# SCH_Aman-PCB-Project_2025-10-18.net
KiCad netlist of a schematic drawn in EasyEDA
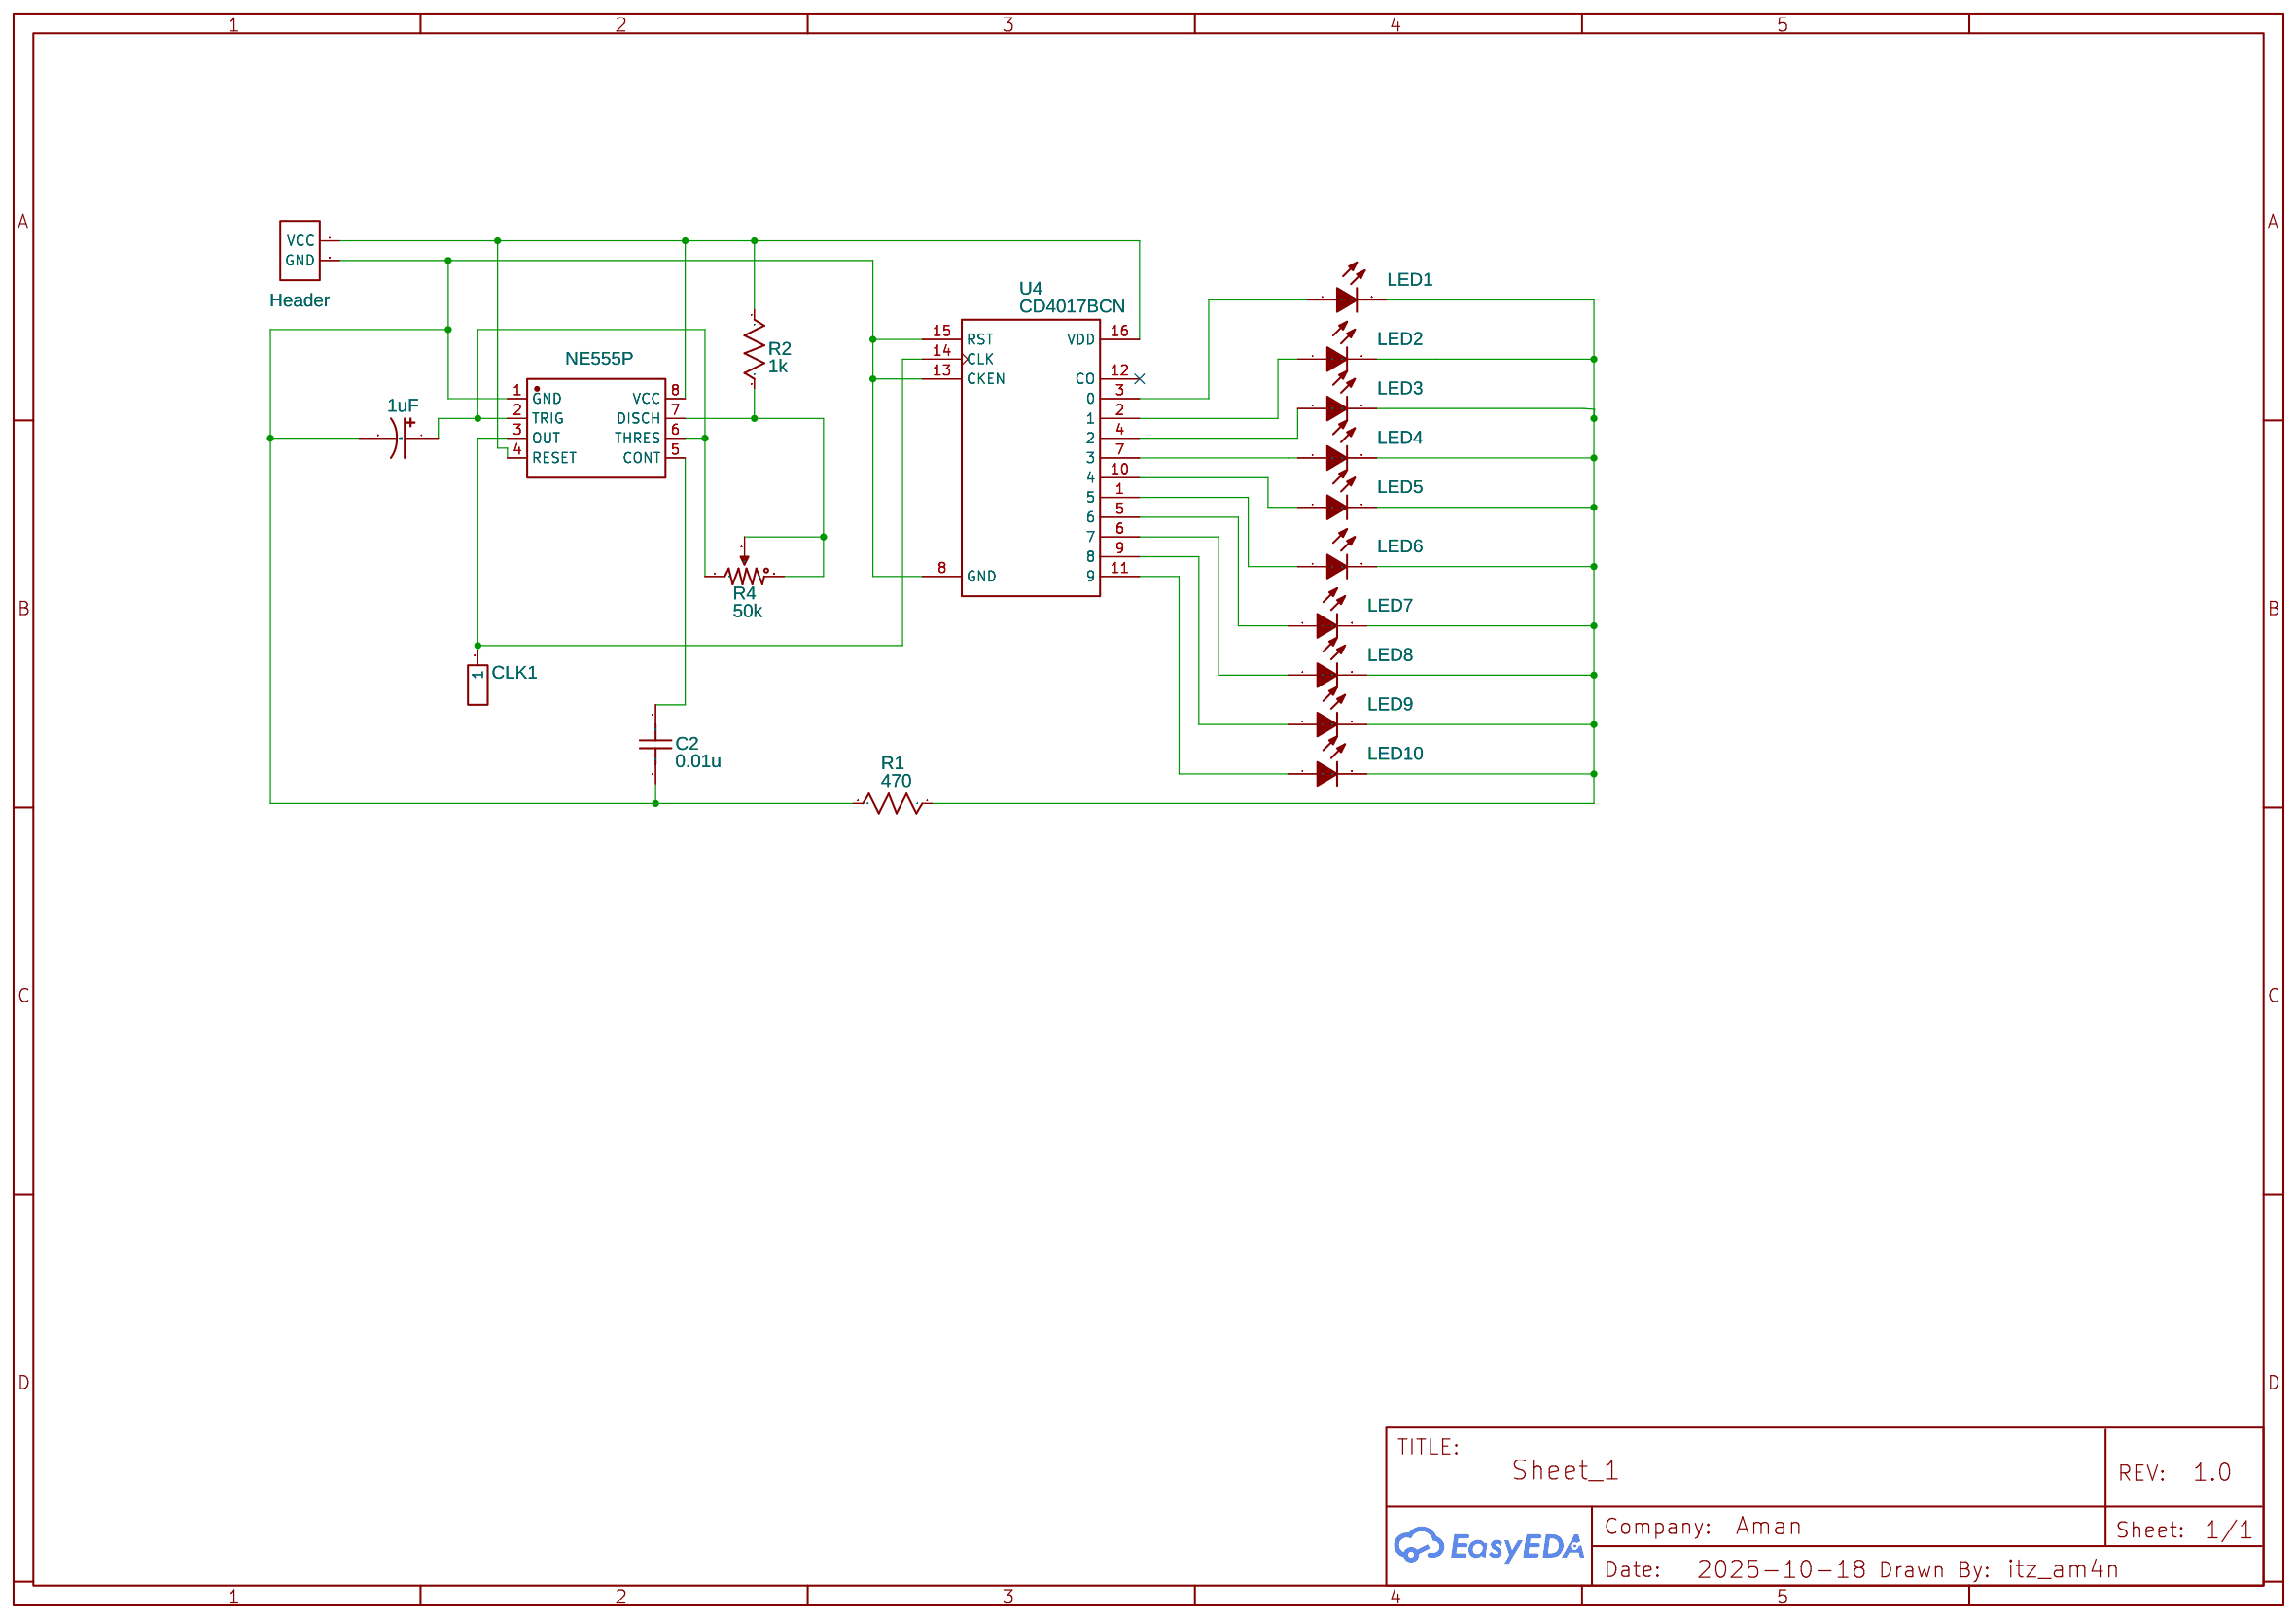
[diagram p0: schematic sheet]

(export (version "E")
  (design (tool "Eeschema 10.0.6"))
  (components
    (comp (ref "C1")
      (value "1uF")
      (fields (field (name "Manufacturer Part") "UVZ1H010MDD") (field (name "Manufacturer") "Nichicon(尼吉康)"))
      (libsource (lib "") (part "UVZ1H010MDD"))
    )
    (comp (ref "C2") (value "0.01u") (libsource (lib "") (part "C_0603_US")))
    (comp (ref "CLK1")
      (value "C81276")
      (fields
        (field (name "Manufacturer Part") "2.54-1*1P针")
        (field (name "Manufacturer") "BOOMELE(Boom Precision Elec)")
      )
      (libsource (lib "") (part "Header-Male-2.54_1x1"))
    )
    (comp (ref "H1") (value "Header") (libsource (lib "") (part "HEADER-FEMALE-2.54_1X2")))
    (comp (ref "LED1") (value "LED_5MM") (libsource (lib "") (part "LED_5MM")))
    (comp (ref "LED2") (value "LED_5MM") (libsource (lib "") (part "LED_5MM")))
    (comp (ref "LED3") (value "LED_5MM") (libsource (lib "") (part "LED_5MM")))
    (comp (ref "LED4") (value "LED_5MM") (libsource (lib "") (part "LED_5MM")))
    (comp (ref "LED5") (value "LED_5MM") (libsource (lib "") (part "LED_5MM")))
    (comp (ref "LED6") (value "LED_5MM") (libsource (lib "") (part "LED_5MM")))
    (comp (ref "LED7") (value "LED_5MM") (libsource (lib "") (part "LED_5MM")))
    (comp (ref "LED8") (value "LED_5MM") (libsource (lib "") (part "LED_5MM")))
    (comp (ref "LED9") (value "LED_5MM") (libsource (lib "") (part "LED_5MM")))
    (comp (ref "LED10") (value "LED_5MM") (libsource (lib "") (part "LED_5MM")))
    (comp (ref "R1")
      (value "470")
      (fields (field (name "Manufacturer Part") "?"))
      (libsource (lib "") (part "Resistor_1"))
    )
    (comp (ref "R2")
      (value "1k")
      (fields (field (name "Manufacturer Part") "?"))
      (libsource (lib "") (part "Resistor"))
    )
    (comp (ref "R4")
      (value "50k")
      (fields (field (name "Manufacturer Part") "?"))
      (libsource (lib "") (part "Potentiometer"))
    )
    (comp (ref "U2")
      (value "NE555P")
      (fields (field (name "Manufacturer") "TI(德州仪器)"))
      (libsource (lib "") (part "NE555P"))
    )
    (comp (ref "U4") (value "CD4017BCN") (libsource (lib "") (part "CD4017BCN")))
  )
  (nets
    (net (code "1") (name "Net-(H1-GND)") (class "Default")
      (node (ref "C1") (pin "2") (pinfunction "2_2") (pintype "unspecified"))
      (node (ref "C2") (pin "2") (pinfunction "2_2") (pintype "unspecified"))
      (node (ref "H1") (pin "2") (pinfunction "GND_2") (pintype "unspecified"))
      (node (ref "R1") (pin "2") (pinfunction "2_2") (pintype "unspecified"))
      (node (ref "U2") (pin "1") (pinfunction "GND_1") (pintype "unspecified"))
      (node (ref "U4") (pin "13") (pinfunction "CKEN_13") (pintype "unspecified"))
      (node (ref "U4") (pin "15") (pinfunction "RST_15") (pintype "unspecified"))
      (node (ref "U4") (pin "8") (pinfunction "GND_8") (pintype "passive"))
    )
    (net (code "2") (name "Net-(H1-VCC)") (class "Default")
      (node (ref "H1") (pin "1") (pinfunction "VCC_1") (pintype "unspecified"))
      (node (ref "R2") (pin "1") (pinfunction "1_1") (pintype "unspecified"))
      (node (ref "U2") (pin "4") (pinfunction "RESET_4") (pintype "unspecified"))
      (node (ref "U2") (pin "8") (pinfunction "VCC_8") (pintype "unspecified"))
      (node (ref "U4") (pin "16") (pinfunction "VDD_16") (pintype "passive"))
    )
    (net (code "3") (name "Net-(LED1-A)") (class "Default")
      (node (ref "LED1") (pin "1") (pinfunction "A_1") (pintype "input"))
      (node (ref "U4") (pin "3") (pinfunction "0_3") (pintype "output"))
    )
    (net (code "4") (name "Net-(LED1-K)") (class "Default")
      (node (ref "LED1") (pin "2") (pinfunction "K_2") (pintype "input"))
      (node (ref "LED10") (pin "2") (pinfunction "K_2") (pintype "input"))
      (node (ref "LED2") (pin "2") (pinfunction "K_2") (pintype "input"))
      (node (ref "LED3") (pin "2") (pinfunction "K_2") (pintype "input"))
      (node (ref "LED4") (pin "2") (pinfunction "K_2") (pintype "input"))
      (node (ref "LED5") (pin "2") (pinfunction "K_2") (pintype "input"))
      (node (ref "LED6") (pin "2") (pinfunction "K_2") (pintype "input"))
      (node (ref "LED7") (pin "2") (pinfunction "K_2") (pintype "input"))
      (node (ref "LED8") (pin "2") (pinfunction "K_2") (pintype "input"))
      (node (ref "LED9") (pin "2") (pinfunction "K_2") (pintype "input"))
      (node (ref "R1") (pin "1") (pinfunction "1_1") (pintype "unspecified"))
    )
    (net (code "5") (name "Net-(LED2-A)") (class "Default")
      (node (ref "LED2") (pin "1") (pinfunction "A_1") (pintype "input"))
      (node (ref "U4") (pin "2") (pinfunction "1_2") (pintype "output"))
    )
    (net (code "6") (name "Net-(LED3-A)") (class "Default")
      (node (ref "LED3") (pin "1") (pinfunction "A_1") (pintype "input"))
      (node (ref "U4") (pin "4") (pinfunction "2_4") (pintype "output"))
    )
    (net (code "7") (name "Net-(LED4-A)") (class "Default")
      (node (ref "LED4") (pin "1") (pinfunction "A_1") (pintype "input"))
      (node (ref "U4") (pin "7") (pinfunction "3_7") (pintype "output"))
    )
    (net (code "8") (name "Net-(LED5-A)") (class "Default")
      (node (ref "LED5") (pin "1") (pinfunction "A_1") (pintype "input"))
      (node (ref "U4") (pin "10") (pinfunction "4_10") (pintype "output"))
    )
    (net (code "9") (name "Net-(LED6-A)") (class "Default")
      (node (ref "LED6") (pin "1") (pinfunction "A_1") (pintype "input"))
      (node (ref "U4") (pin "1") (pinfunction "5_1") (pintype "output"))
    )
    (net (code "10") (name "Net-(LED7-A)") (class "Default")
      (node (ref "LED7") (pin "1") (pinfunction "A_1") (pintype "input"))
      (node (ref "U4") (pin "5") (pinfunction "6_5") (pintype "output"))
    )
    (net (code "11") (name "Net-(LED8-A)") (class "Default")
      (node (ref "LED8") (pin "1") (pinfunction "A_1") (pintype "input"))
      (node (ref "U4") (pin "6") (pinfunction "7_6") (pintype "output"))
    )
    (net (code "12") (name "Net-(LED9-A)") (class "Default")
      (node (ref "LED9") (pin "1") (pinfunction "A_1") (pintype "input"))
      (node (ref "U4") (pin "9") (pinfunction "8_9") (pintype "output"))
    )
    (net (code "13") (name "Net-(LED10-A)") (class "Default")
      (node (ref "LED10") (pin "1") (pinfunction "A_1") (pintype "input"))
      (node (ref "U4") (pin "11") (pinfunction "9_11") (pintype "output"))
    )
    (net (code "14") (name "Net-(R4-2)") (class "Default")
      (node (ref "R2") (pin "2") (pinfunction "2_2") (pintype "unspecified"))
      (node (ref "R4") (pin "2") (pinfunction "3_2") (pintype "unspecified"))
      (node (ref "R4") (pin "3") (pinfunction "2_3") (pintype "unspecified"))
      (node (ref "U2") (pin "7") (pinfunction "DISCH_7") (pintype "unspecified"))
    )
    (net (code "15") (name "Net-(U2-CONT)") (class "Default")
      (node (ref "C2") (pin "1") (pinfunction "1_1") (pintype "unspecified"))
      (node (ref "U2") (pin "5") (pinfunction "CONT_5") (pintype "unspecified"))
    )
    (net (code "16") (name "Net-(U2-OUT)") (class "Default")
      (node (ref "CLK1") (pin "1") (pinfunction "1_1") (pintype "unspecified"))
      (node (ref "U2") (pin "3") (pinfunction "OUT_3") (pintype "unspecified"))
      (node (ref "U4") (pin "14") (pinfunction "CLK_14") (pintype "unspecified"))
    )
    (net (code "17") (name "Net-(U2-THRES)") (class "Default")
      (node (ref "C1") (pin "1") (pinfunction "1_1") (pintype "unspecified"))
      (node (ref "R4") (pin "1") (pinfunction "1_1") (pintype "unspecified"))
      (node (ref "U2") (pin "2") (pinfunction "TRIG_2") (pintype "unspecified"))
      (node (ref "U2") (pin "6") (pinfunction "THRES_6") (pintype "unspecified"))
    )
    (net (code "18") (name "unconnected-(U4-CO-Pad12)") (class "Default")
      (node (ref "U4") (pin "12") (pinfunction "CO_12") (pintype "output+no_connect"))
    )
  )
)
